# PowerSwitch.net
KiCad netlist of a schematic drawn in Altium Designer
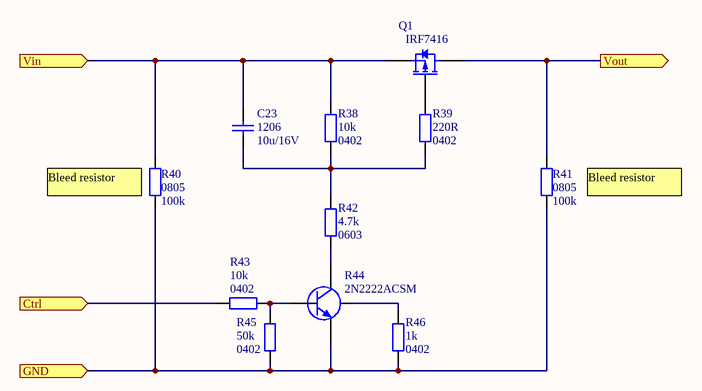
[diagram p0: PowerSwitch.SchDoc]

(export (version "E")
  (design (tool "Eeschema 10.0.6"))
  (components
    (comp (ref "C23")
      (value "10u/16V")
      (footprint "SMD_Capacitor_1206")
      (description "Ceramic Cap Kemet COTS 10u/16V X7R 1206")
      (fields
        (field (name "MANUFACTURERPARTNUMBER") "C1206T106K4RACTU")
        (field (name "MANUFACTURER") "Kemet")
        (field (name "PACKGE") "1206")
      )
      (libsource (lib "capacitors") (part "Cer_C1206T106K4RACTU"))
    )
    (comp (ref "Q1")
      (value "IRF7416")
      (footprint "SOIC-8-N_SSSGDDDD")
      (description "10A/30V HEXFET Power P-MOSFET.")
      (fields (field (name "MANUFACTURER") "International Rectifier"))
      (libsource (lib "transistors") (part "IRF7416"))
    )
    (comp (ref "R38")
      (value "10k")
      (footprint "SMD_Resistor_0402")
      (description "10k/1% Vishay CRCW 0402 Resistor. 63mW, 100ppm, 50V.")
      (fields
        (field (name "MANUFACTURER") "Vishay")
        (field (name "MANUFACTURERPARTNUMBER") "CRCW040210K0FKxxxx")
        (field (name "PACKAGE") "0402")
      )
      (libsource (lib "resistors") (part "CRCW040210K0FKxxxx"))
    )
    (comp (ref "R39")
      (value "220R")
      (footprint "SMD_Resistor_0402")
      (description "220R/1% Vishay CRCW 0402 Resistor. 63mW, 100ppm, 50V.")
      (fields
        (field (name "MANUFACTURER") "Vishay")
        (field (name "MANUFACTURERPARTNUMBER") "CRCW0402220RFKxxxx")
        (field (name "PACKAGE") "0402")
      )
      (libsource (lib "resistors") (part "CRCW0402220RFKxxxx"))
    )
    (comp (ref "R40")
      (value "0805")
      (footprint "Resistor 0805")
      (description "Resistor")
      (fields (field (name "ALTIUM_VALUE") "100k") (field (name "PUBLISHER") "Altium Limited"))
      (libsource (lib "Miscellaneous Devices") (part "Res2"))
    )
    (comp (ref "R41")
      (value "0805")
      (footprint "Resistor 0805")
      (description "Resistor")
      (fields (field (name "ALTIUM_VALUE") "100k") (field (name "PUBLISHER") "Altium Limited"))
      (libsource (lib "Miscellaneous Devices") (part "Res2"))
    )
    (comp (ref "R42")
      (value "4.7k")
      (footprint "SMD_Resistor_0603")
      (description "4.7k/1% Vishay CRCW 0603 Resistor. 100mW, 100ppm, 75V.")
      (fields
        (field (name "MANUFACTURER") "Vishay")
        (field (name "MANUFACTUERPARTNUMBER") "CRCW06034K70FKxxxx")
        (field (name "PACKAGE") "0603")
      )
      (libsource (lib "resistors") (part "CRCW06034K70FKxxxx"))
    )
    (comp (ref "R43")
      (value "10k")
      (footprint "SMD_Resistor_0402")
      (description "10k/1% Vishay CRCW 0402 Resistor. 63mW, 100ppm, 50V.")
      (fields
        (field (name "MANUFACTURER") "Vishay")
        (field (name "MANUFACTURERPARTNUMBER") "CRCW040210K0FKxxxx")
        (field (name "PACKAGE") "0402")
      )
      (libsource (lib "") (part "CRCW040210K0FKxxxx_1"))
    )
    (comp (ref "R44")
      (value "2N2222ACSM")
      (footprint "LCC1-4_BEC")
      (description "Silicon Planar Epitaxial NPN Transistor.")
      (fields (field (name "MANUFACTURER") "Semelab-TT"))
      (libsource (lib "transistors") (part "2N2222ACSM"))
    )
    (comp (ref "R45")
      (value "50k")
      (footprint "SMD_Resistor_0402")
      (description "100k/1% Vishay CRCW 0402 Resistor. 63mW, 100ppm, 50V.")
      (fields
        (field (name "MANUFACTURER") "Vishay")
        (field (name "MANUFACTURERPARTNUMBER") "CRCW0402100KFKxxxx")
        (field (name "PACKAGE") "0402")
      )
      (libsource (lib "resistors") (part "CRCW0402100KFKxxxx"))
    )
    (comp (ref "R46")
      (value "1k")
      (footprint "SMD_Resistor_0402")
      (description "1k/1% Vishay CRCW 0402 Resistor. 63mW, 100ppm, 50V.")
      (fields
        (field (name "MANUFACTURER") "Vishay")
        (field (name "MANUFACTURERPARTNUMBER") "CRCW04021K00FKxxxx")
        (field (name "PACKAGE") "0402")
      )
      (libsource (lib "resistors") (part "CRCW04021K00FKxxxx"))
    )
  )
  (nets
    (net (code "1") (name "/Ctrl") (class "Default")
      (node (ref "R43") (pin "1") (pinfunction "1_1") (pintype "passive"))
    )
    (net (code "2") (name "/GND") (class "Default")
      (node (ref "R40") (pin "1") (pinfunction "1_1") (pintype "passive"))
      (node (ref "R41") (pin "1") (pinfunction "1_1") (pintype "passive"))
      (node (ref "R44") (pin "E") (pinfunction "E_E") (pintype "passive"))
      (node (ref "R45") (pin "2") (pinfunction "2_2") (pintype "passive"))
      (node (ref "R46") (pin "1") (pinfunction "1_1") (pintype "passive"))
    )
    (net (code "3") (name "/Vin") (class "Default")
      (node (ref "C23") (pin "1") (pinfunction "1_1") (pintype "passive"))
      (node (ref "Q1") (pin "S") (pinfunction "S_S") (pintype "passive"))
      (node (ref "R38") (pin "1") (pinfunction "1_1") (pintype "passive"))
      (node (ref "R40") (pin "2") (pinfunction "2_2") (pintype "passive"))
    )
    (net (code "4") (name "/Vout") (class "Default")
      (node (ref "Q1") (pin "D") (pinfunction "D_D") (pintype "passive"))
      (node (ref "R41") (pin "2") (pinfunction "2_2") (pintype "passive"))
    )
    (net (code "5") (name "Net-(C23-Pad2)") (class "Default")
      (node (ref "C23") (pin "2") (pinfunction "2_2") (pintype "passive"))
      (node (ref "R38") (pin "2") (pinfunction "2_2") (pintype "passive"))
      (node (ref "R39") (pin "2") (pinfunction "2_2") (pintype "passive"))
      (node (ref "R42") (pin "1") (pinfunction "1_1") (pintype "passive"))
    )
    (net (code "6") (name "Net-(Q1-PadG)") (class "Default")
      (node (ref "Q1") (pin "G") (pinfunction "G_G") (pintype "passive"))
      (node (ref "R39") (pin "1") (pinfunction "1_1") (pintype "passive"))
    )
    (net (code "7") (name "Net-(R42-Pad2)") (class "Default")
      (node (ref "R42") (pin "2") (pinfunction "2_2") (pintype "passive"))
      (node (ref "R44") (pin "C") (pinfunction "C_C") (pintype "passive"))
    )
    (net (code "8") (name "Net-(R43-Pad2)") (class "Default")
      (node (ref "R43") (pin "2") (pinfunction "2_2") (pintype "passive"))
      (node (ref "R44") (pin "B") (pinfunction "B_B") (pintype "passive"))
      (node (ref "R45") (pin "1") (pinfunction "1_1") (pintype "passive"))
    )
    (net (code "9") (name "Net-(R44-PadShield)") (class "Default")
      (node (ref "R44") (pin "Shield") (pinfunction "Shield_Shield") (pintype "passive"))
      (node (ref "R46") (pin "2") (pinfunction "2_2") (pintype "passive"))
    )
  )
)
